# PIC32.net
KiCad netlist of a schematic drawn in Altium Designer
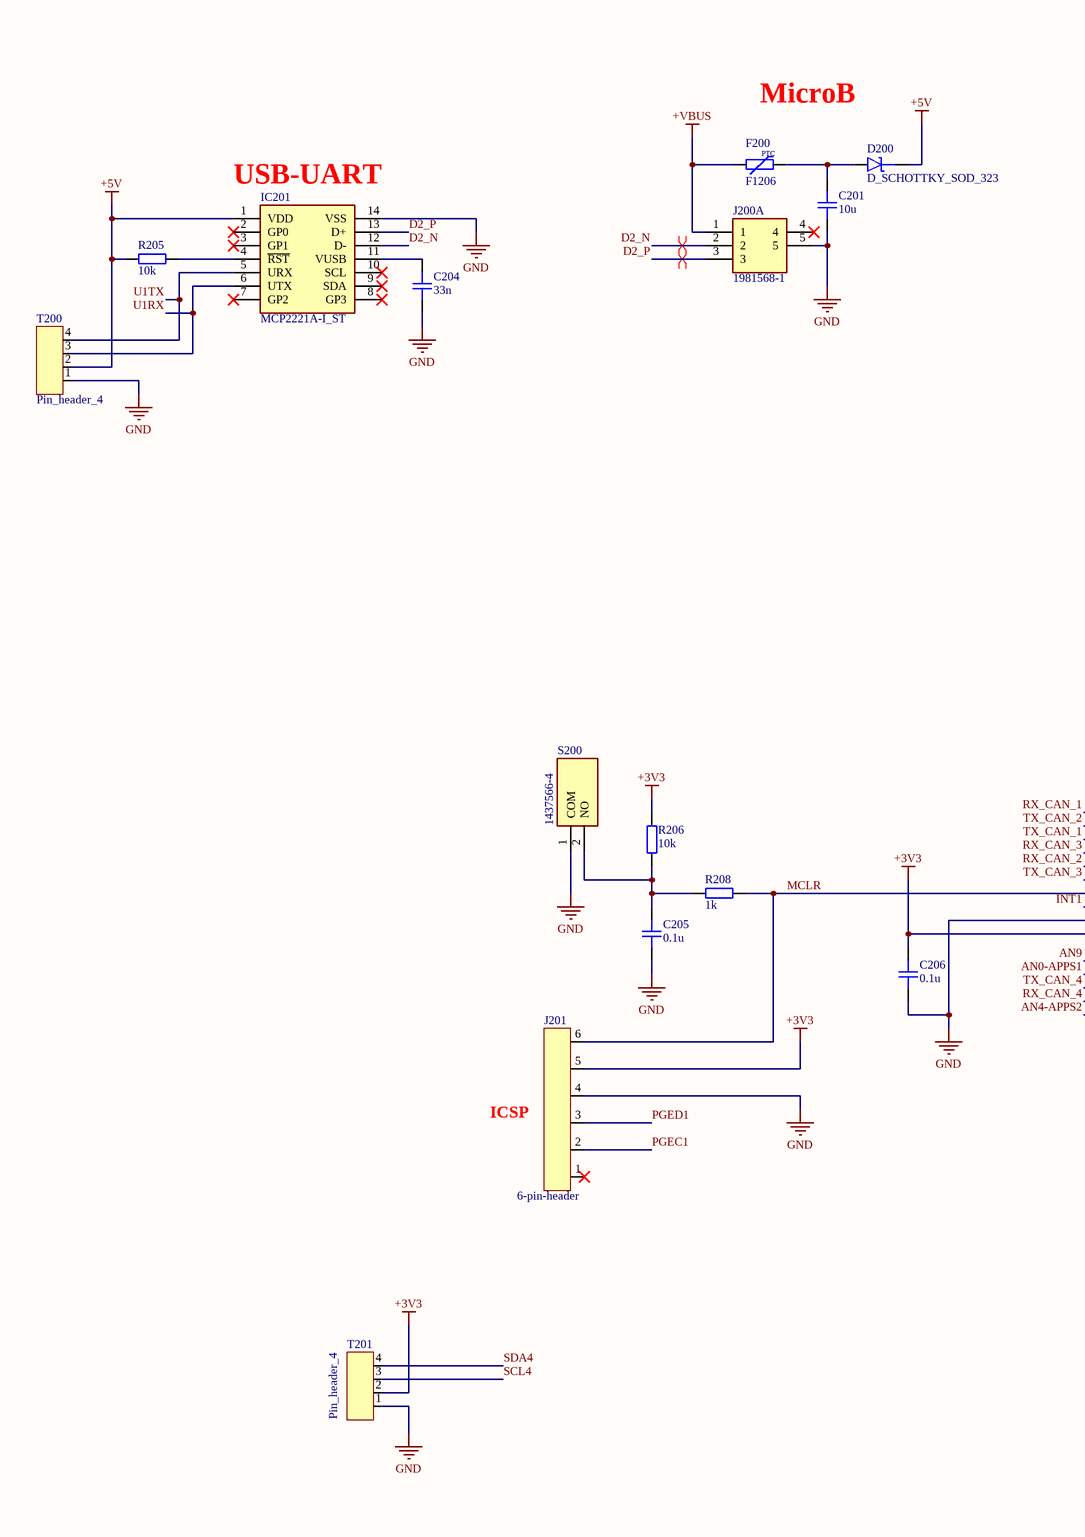
[diagram p0: PIC32.SchDoc, left]
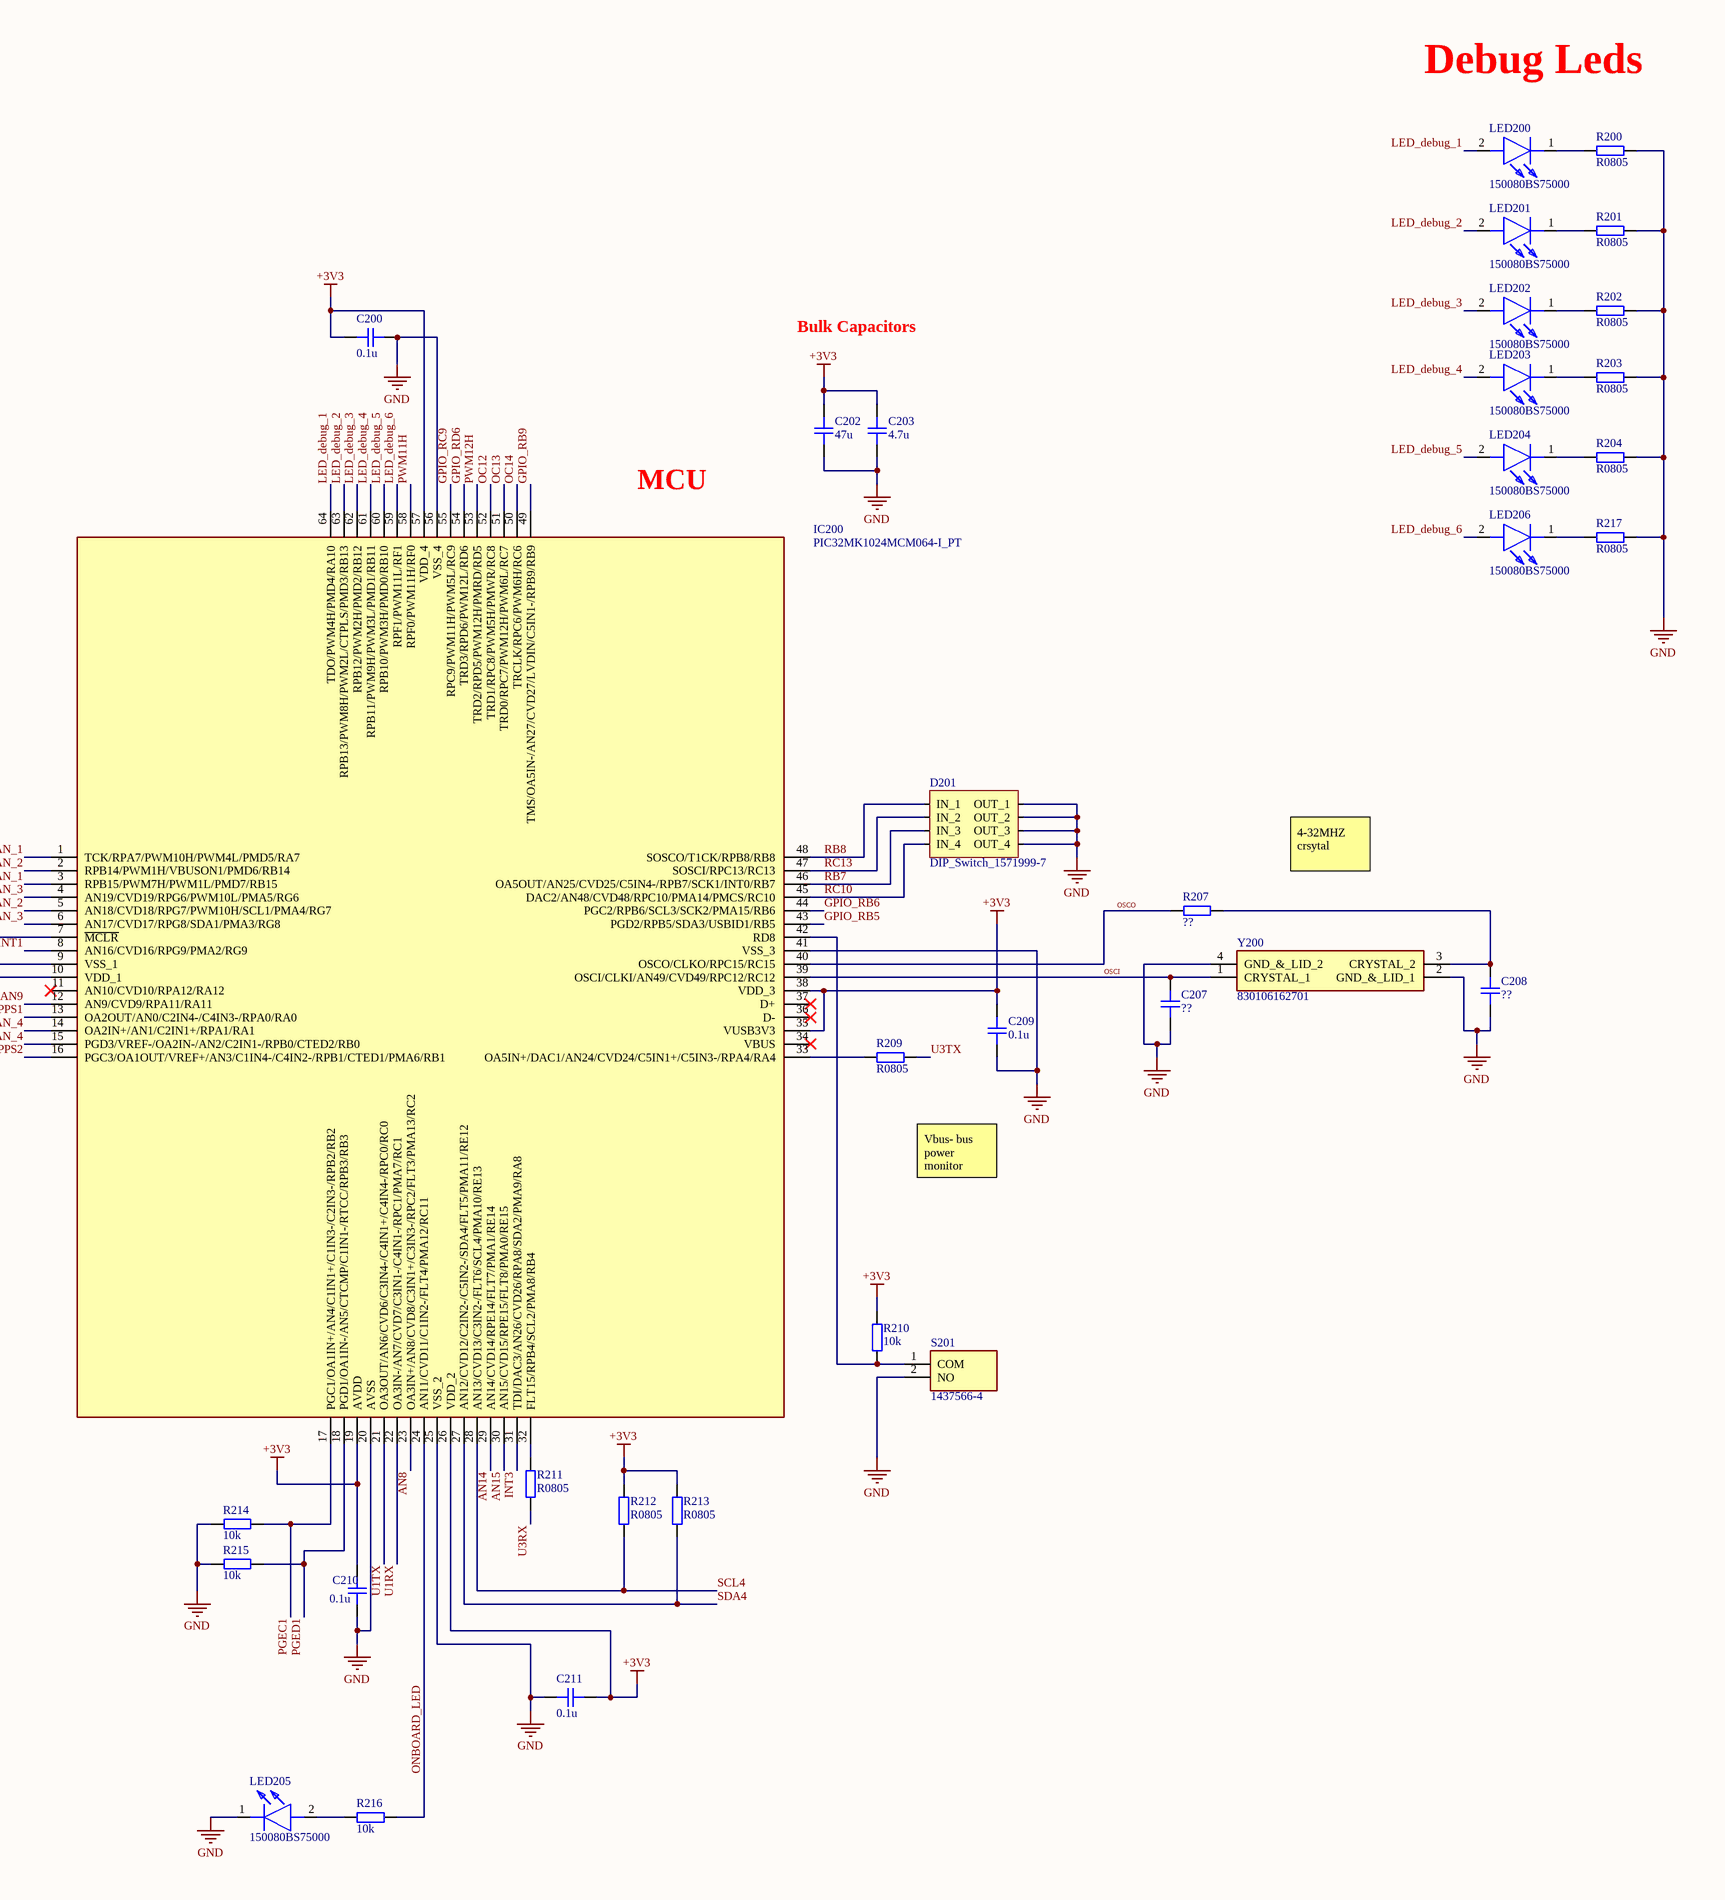
[diagram p1: PIC32.SchDoc, right]

(export (version "E")
  (design (tool "Eeschema 10.0.6"))
  (components
    (comp (ref "C200")
      (value "0.1u")
      (footprint "CAP_0805")
      (description "Capacitor SMD 0805 16V")
      (libsource (lib "Pedro_Integrated_Library") (part "CAP_0805_16V"))
    )
    (comp (ref "C201")
      (value "10u")
      (footprint "CAP_0805")
      (description "Capacitor SMD 0805 10V")
      (libsource (lib "Schematic-Lib-PhilsLab") (part "CAP_0805_10V"))
    )
    (comp (ref "C202")
      (value "47u")
      (footprint "CAP_0805")
      (description "Capacitor SMD 0805 16V")
      (libsource (lib "Pedro_Integrated_Library") (part "CAP_0805_16V"))
    )
    (comp (ref "C203")
      (value "4.7u")
      (footprint "CAP_0805")
      (description "Capacitor SMD 0805 16V")
      (libsource (lib "Pedro_Integrated_Library") (part "CAP_0805_16V"))
    )
    (comp (ref "C204")
      (value "33n")
      (footprint "CAP_0805")
      (description "Capacitor SMD 0805 10V")
      (libsource (lib "Schematic-Lib-PhilsLab") (part "CAP_0805_10V"))
    )
    (comp (ref "C205")
      (value "0.1u")
      (footprint "CAP_0805")
      (description "Capacitor SMD 0805 16V")
      (libsource (lib "Pedro_Integrated_Library") (part "CAP_0805_16V"))
    )
    (comp (ref "C206")
      (value "0.1u")
      (footprint "CAP_0805")
      (description "Capacitor SMD 0805 16V")
      (libsource (lib "Pedro_Integrated_Library") (part "CAP_0805_16V"))
    )
    (comp (ref "C207")
      (value "??")
      (footprint "CAP_0805")
      (description "Capacitor SMD 0805 16V")
      (libsource (lib "Pedro_Integrated_Library") (part "CAP_0805_16V"))
    )
    (comp (ref "C208")
      (value "??")
      (footprint "CAP_0805")
      (description "Capacitor SMD 0805 16V")
      (libsource (lib "Pedro_Integrated_Library") (part "CAP_0805_16V"))
    )
    (comp (ref "C209")
      (value "0.1u")
      (footprint "CAP_0805")
      (description "Capacitor SMD 0805 16V")
      (libsource (lib "Pedro_Integrated_Library") (part "CAP_0805_16V"))
    )
    (comp (ref "C210")
      (value "0.1u")
      (footprint "CAP_0805")
      (description "Capacitor SMD 0805 16V")
      (libsource (lib "Pedro_Integrated_Library") (part "CAP_0805_16V"))
    )
    (comp (ref "C211")
      (value "0.1u")
      (footprint "CAP_0805")
      (description "Capacitor SMD 0805 16V")
      (libsource (lib "Pedro_Integrated_Library") (part "CAP_0805_16V"))
    )
    (comp (ref "D200")
      (value "D_SCHOTTKY_SOD_323")
      (footprint "SOD-323")
      (description "Diode Schottky SMD SOD-323")
      (libsource (lib "PhilsLab") (part "D_SCHOTTKY_SOD_323"))
    )
    (comp (ref "D201")
      (value "DIP_Switch_1571999-7")
      (footprint "DIP_Switch_1571999-7 - duplicate")
      (libsource (lib "Pedro_sch_lib") (part "DIP_Switch_1571999-7"))
    )
    (comp (ref "F200")
      (value "F1206")
      (footprint "FUSE_1206")
      (description "Fuse PPTC SMD 1206")
      (libsource (lib "Schematic-Lib-PhilsLab") (part "FUSE_PPTC_1206"))
    )
    (comp (ref "IC200")
      (value "PIC32MK1024MCM064-I_PT")
      (footprint "QFP50P1200X1200X120-64N")
      (description "Integrated Circuit")
      (fields
        (field (name "MANUFACTURER_PART_NUMBER") "PIC32MK1024MCM064-I/PT")
        (field (name "MOUSER PART NUMBER") "579-2MK1024MCM064IPT")
      )
      (libsource (lib "Pedro_Integrated_Library") (part "PIC32MK1024MCM064-I_PT"))
    )
    (comp (ref "IC201")
      (value "MCP2221A-I_ST")
      (footprint "SOP65P640X120-14N")
      (description "Integrated Circuit")
      (fields
        (field (name "MANUFACTURER_PART_NUMBER") "MCP2221A-I/ST")
        (field (name "MOUSER PART NUMBER") "579-MCP2221A-I/ST")
      )
      (libsource (lib "*") (part "MCP2221A-I_ST"))
    )
    (comp (ref "J200")
      (value "1981568-1")
      (footprint "1981568-1")
      (description "Connector")
      (fields (field (name "MOUSER PART NUMBER") "571-1981568-1"))
      (libsource (lib "Pedro_sch_lib") (part "1981568-1"))
    )
    (comp (ref "J201")
      (value "6-pin-header")
      (footprint "G800W302018EU")
      (description "Pin Header 6 Position 2.54mm Pitch")
      (fields
        (field (name "MANUFACTURER") "Amphenol")
        (field (name "MANUFACTURER PART NUMBER") "G800W302018EU")
      )
      (libsource (lib "PhilsLab") (part "G800W302018EU"))
    )
    (comp (ref "LED200")
      (value "150080BS75000")
      (footprint "LEDC2012X80N")
      (description "LED")
      (fields (field (name "MOUSER PART NUMBER") "710-150080BS75000"))
      (libsource (lib "Pedro_Integrated_Library") (part "150080BS75000"))
    )
    (comp (ref "LED201")
      (value "150080BS75000")
      (footprint "LEDC2012X80N")
      (description "LED")
      (fields (field (name "MOUSER PART NUMBER") "710-150080BS75000"))
      (libsource (lib "Pedro_Integrated_Library") (part "150080BS75000"))
    )
    (comp (ref "LED202")
      (value "150080BS75000")
      (footprint "LEDC2012X80N")
      (description "LED")
      (fields (field (name "MOUSER PART NUMBER") "710-150080BS75000"))
      (libsource (lib "Pedro_Integrated_Library") (part "150080BS75000"))
    )
    (comp (ref "LED203")
      (value "150080BS75000")
      (footprint "LEDC2012X80N")
      (description "LED")
      (fields (field (name "MOUSER PART NUMBER") "710-150080BS75000"))
      (libsource (lib "Pedro_Integrated_Library") (part "150080BS75000"))
    )
    (comp (ref "LED204")
      (value "150080BS75000")
      (footprint "LEDC2012X80N")
      (description "LED")
      (fields (field (name "MOUSER PART NUMBER") "710-150080BS75000"))
      (libsource (lib "Pedro_Integrated_Library") (part "150080BS75000"))
    )
    (comp (ref "LED205")
      (value "150080BS75000")
      (footprint "LEDC2012X80N")
      (description "LED")
      (fields (field (name "MOUSER PART NUMBER") "710-150080BS75000"))
      (libsource (lib "Pedro_Integrated_Library") (part "150080BS75000"))
    )
    (comp (ref "LED206")
      (value "150080BS75000")
      (footprint "LEDC2012X80N")
      (description "LED")
      (fields (field (name "MOUSER PART NUMBER") "710-150080BS75000"))
      (libsource (lib "Pedro_Integrated_Library") (part "150080BS75000"))
    )
    (comp (ref "R200")
      (value "R0805")
      (footprint "RES_0805")
      (description "Resistor SMD 0805")
      (libsource (lib "Schematic-Lib-PhilsLab") (part "RES_0805"))
    )
    (comp (ref "R201")
      (value "R0805")
      (footprint "RES_0805")
      (description "Resistor SMD 0805")
      (libsource (lib "Schematic-Lib-PhilsLab") (part "RES_0805"))
    )
    (comp (ref "R202")
      (value "R0805")
      (footprint "RES_0805")
      (description "Resistor SMD 0805")
      (libsource (lib "Schematic-Lib-PhilsLab") (part "RES_0805"))
    )
    (comp (ref "R203")
      (value "R0805")
      (footprint "RES_0805")
      (description "Resistor SMD 0805")
      (libsource (lib "Schematic-Lib-PhilsLab") (part "RES_0805"))
    )
    (comp (ref "R204")
      (value "R0805")
      (footprint "RES_0805")
      (description "Resistor SMD 0805")
      (libsource (lib "Schematic-Lib-PhilsLab") (part "RES_0805"))
    )
    (comp (ref "R205")
      (value "10k")
      (footprint "RES_0805")
      (description "Resistor SMD 0805")
      (libsource (lib "Pedro_Integrated_Library") (part "RES_0805"))
    )
    (comp (ref "R206")
      (value "10k")
      (footprint "RES_0805")
      (description "Resistor SMD 0805")
      (libsource (lib "Pedro_Integrated_Library") (part "RES_0805"))
    )
    (comp (ref "R207")
      (value "??")
      (footprint "RES_0805")
      (description "Resistor SMD 0805")
      (libsource (lib "Pedro_Integrated_Library") (part "RES_0805"))
    )
    (comp (ref "R208")
      (value "1k")
      (footprint "RES_0805")
      (description "Resistor SMD 0805")
      (libsource (lib "Pedro_Integrated_Library") (part "RES_0805"))
    )
    (comp (ref "R209")
      (value "R0805")
      (footprint "RES_0805")
      (description "Resistor SMD 0805")
      (libsource (lib "Schematic-Lib-PhilsLab") (part "RES_0805"))
    )
    (comp (ref "R210")
      (value "10k")
      (footprint "RES_0805")
      (description "Resistor SMD 0805")
      (libsource (lib "Pedro_Integrated_Library") (part "RES_0805"))
    )
    (comp (ref "R211")
      (value "R0805")
      (footprint "RES_0805")
      (description "Resistor SMD 0805")
      (libsource (lib "Schematic-Lib-PhilsLab") (part "RES_0805"))
    )
    (comp (ref "R212")
      (value "R0805")
      (footprint "RES_0805")
      (description "Resistor SMD 0805")
      (libsource (lib "Schematic-Lib-PhilsLab") (part "RES_0805"))
    )
    (comp (ref "R213")
      (value "R0805")
      (footprint "RES_0805")
      (description "Resistor SMD 0805")
      (libsource (lib "Schematic-Lib-PhilsLab") (part "RES_0805"))
    )
    (comp (ref "R214")
      (value "10k")
      (footprint "RES_0805")
      (description "Resistor SMD 0805")
      (libsource (lib "Pedro_Integrated_Library") (part "RES_0805"))
    )
    (comp (ref "R215")
      (value "10k")
      (footprint "RES_0805")
      (description "Resistor SMD 0805")
      (libsource (lib "Pedro_Integrated_Library") (part "RES_0805"))
    )
    (comp (ref "R216")
      (value "10k")
      (footprint "RES_0805")
      (description "Resistor SMD 0805")
      (libsource (lib "Pedro_Integrated_Library") (part "RES_0805"))
    )
    (comp (ref "R217")
      (value "R0805")
      (footprint "RES_0805")
      (description "Resistor SMD 0805")
      (libsource (lib "Schematic-Lib-PhilsLab") (part "RES_0805"))
    )
    (comp (ref "S200")
      (value "1437566-4")
      (footprint "14375664")
      (description "Switch")
      (libsource (lib "Pedro_sch_lib") (part "1437566-4"))
    )
    (comp (ref "S201")
      (value "1437566-4")
      (footprint "14375664")
      (description "Switch")
      (libsource (lib "") (part "1437566-4_1"))
    )
    (comp (ref "T200")
      (value "Pin_header_4")
      (footprint "Pin_header_4")
      (libsource (lib "Pedro_Integrated_Library") (part "Pin_header_4"))
    )
    (comp (ref "T201")
      (value "Pin_header_4")
      (footprint "Pin_header_4")
      (libsource (lib "Pedro_Integrated_Library") (part "Pin_header_4"))
    )
    (comp (ref "Y200")
      (value "830106162701")
      (footprint "Pedro_pcb_lib:830106162701")
      (description "Crystal or Oscillator")
      (fields (field (name "MOUSER PART NUMBER") "710-830106162701"))
      (libsource (lib "*") (part "830106162701"))
    )
  )
  (nets
    (net (code "1") (name "+3V3") (class "Default")
      (node (ref "C200") (pin "1") (pinfunction "1_1") (pintype "passive"))
      (node (ref "C202") (pin "1") (pinfunction "1_1") (pintype "passive"))
      (node (ref "C203") (pin "1") (pinfunction "1_1") (pintype "passive"))
      (node (ref "C206") (pin "2") (pinfunction "2_2") (pintype "passive"))
      (node (ref "C209") (pin "1") (pinfunction "1_1") (pintype "passive"))
      (node (ref "C210") (pin "2") (pinfunction "2_2") (pintype "passive"))
      (node (ref "C211") (pin "1") (pinfunction "1_1") (pintype "passive"))
      (node (ref "IC200") (pin "10") (pinfunction "VDD_1_10") (pintype "passive"))
      (node (ref "IC200") (pin "19") (pinfunction "AVDD_19") (pintype "passive"))
      (node (ref "IC200") (pin "26") (pinfunction "VDD_2_26") (pintype "passive"))
      (node (ref "IC200") (pin "35") (pinfunction "VUSB3V3_35") (pintype "passive"))
      (node (ref "IC200") (pin "38") (pinfunction "VDD_3_38") (pintype "passive"))
      (node (ref "IC200") (pin "57") (pinfunction "VDD_4_57") (pintype "passive"))
      (node (ref "J201") (pin "5") (pinfunction "5_5") (pintype "passive"))
      (node (ref "R206") (pin "1") (pinfunction "1_1") (pintype "passive"))
      (node (ref "R210") (pin "2") (pinfunction "2_2") (pintype "passive"))
      (node (ref "R212") (pin "1") (pinfunction "1_1") (pintype "passive"))
      (node (ref "R213") (pin "1") (pinfunction "1_1") (pintype "passive"))
      (node (ref "T201") (pin "2") (pintype "bidirectional"))
    )
    (net (code "2") (name "+5V") (class "Default")
      (node (ref "D200") (pin "K") (pinfunction "K_K") (pintype "passive"))
      (node (ref "IC201") (pin "1") (pinfunction "VDD_1") (pintype "passive"))
      (node (ref "R205") (pin "1") (pinfunction "1_1") (pintype "passive"))
      (node (ref "T200") (pin "2") (pintype "bidirectional"))
    )
    (net (code "3") (name "+VBUS") (class "Default")
      (node (ref "F200") (pin "1") (pinfunction "1_1") (pintype "passive"))
      (node (ref "J200") (pin "1") (pinfunction "1_1") (pintype "passive"))
    )
    (net (code "4") (name "/AN0-APPS1") (class "Default")
      (node (ref "IC200") (pin "13") (pinfunction "OA2OUT/AN0/C2IN4-/C4IN3-/RPA0/RA0_13") (pintype "passive"))
    )
    (net (code "5") (name "/AN4-APPS2") (class "Default")
      (node (ref "IC200") (pin "16") (pinfunction "PGC3/OA1OUT/VREF+/AN3/C1IN4-/C4IN2-/RPB1/CTED1/PMA6/RB1_16") (pintype "passive"))
    )
    (net (code "6") (name "/AN8") (class "Default")
      (node (ref "IC200") (pin "23") (pinfunction "OA3IN+/AN8/CVD8/C3IN1+/C3IN3-/RPC2/FLT3/PMA13/RC2_23") (pintype "passive"))
    )
    (net (code "7") (name "/AN9") (class "Default")
      (node (ref "IC200") (pin "12") (pinfunction "AN9/CVD9/RPA11/RA11_12") (pintype "passive"))
    )
    (net (code "8") (name "/AN14") (class "Default")
      (node (ref "IC200") (pin "29") (pinfunction "AN14/CVD14/RPE14/FLT7/PMA1/RE14_29") (pintype "passive"))
    )
    (net (code "9") (name "/AN15") (class "Default")
      (node (ref "IC200") (pin "30") (pinfunction "AN15/CVD15/RPE15/FLT8/PMA0/RE15_30") (pintype "passive"))
    )
    (net (code "10") (name "/D2_N") (class "Default")
      (node (ref "IC201") (pin "12") (pinfunction "D-_12") (pintype "passive"))
      (node (ref "J200") (pin "2") (pinfunction "2_2") (pintype "passive"))
    )
    (net (code "11") (name "/D2_P") (class "Default")
      (node (ref "IC201") (pin "13") (pinfunction "D+_13") (pintype "passive"))
      (node (ref "J200") (pin "3") (pinfunction "3_3") (pintype "passive"))
    )
    (net (code "12") (name "/GPIO_RB5") (class "Default")
      (node (ref "IC200") (pin "43") (pinfunction "PGD2/RPB5/SDA3/USBID1/RB5_43") (pintype "passive"))
    )
    (net (code "13") (name "/GPIO_RB6") (class "Default")
      (node (ref "IC200") (pin "44") (pinfunction "PGC2/RPB6/SCL3/SCK2/PMA15/RB6_44") (pintype "passive"))
    )
    (net (code "14") (name "/GPIO_RB9") (class "Default")
      (node (ref "IC200") (pin "49") (pinfunction "TMS/OA5IN-/AN27/CVD27/LVDIN/C5IN1-/RPB9/RB9_49") (pintype "passive"))
    )
    (net (code "15") (name "/GPIO_RC9") (class "Default")
      (node (ref "IC200") (pin "55") (pinfunction "RPC9/PWM11H/PWM5L/RC9_55") (pintype "passive"))
    )
    (net (code "16") (name "/GPIO_RD6") (class "Default")
      (node (ref "IC200") (pin "54") (pinfunction "TRD3/RPD6/PWM12L/RD6_54") (pintype "passive"))
    )
    (net (code "17") (name "/INT1") (class "Default")
      (node (ref "IC200") (pin "8") (pinfunction "AN16/CVD16/RPG9/PMA2/RG9_8") (pintype "passive"))
    )
    (net (code "18") (name "/INT3") (class "Default")
      (node (ref "IC200") (pin "31") (pinfunction "TDI/DAC3/AN26/CVD26/RPA8/SDA2/PMA9/RA8_31") (pintype "passive"))
    )
    (net (code "19") (name "/LED_debug_1") (class "Default")
      (node (ref "IC200") (pin "64") (pinfunction "TDO/PWM4H/PMD4/RA10_64") (pintype "passive"))
      (node (ref "LED200") (pin "2") (pinfunction "A_2") (pintype "passive"))
    )
    (net (code "20") (name "/LED_debug_2") (class "Default")
      (node (ref "IC200") (pin "63") (pinfunction "RPB13/PWM8H/PWM2L/CTPLS/PMD3/RB13_63") (pintype "passive"))
      (node (ref "LED201") (pin "2") (pinfunction "A_2") (pintype "passive"))
    )
    (net (code "21") (name "/LED_debug_3") (class "Default")
      (node (ref "IC200") (pin "62") (pinfunction "RPB12/PWM2H/PMD2/RB12_62") (pintype "passive"))
      (node (ref "LED202") (pin "2") (pinfunction "A_2") (pintype "passive"))
    )
    (net (code "22") (name "/LED_debug_4") (class "Default")
      (node (ref "IC200") (pin "61") (pinfunction "RPB11/PWM9H/PWM3L/PMD1/RB11_61") (pintype "passive"))
      (node (ref "LED203") (pin "2") (pinfunction "A_2") (pintype "passive"))
    )
    (net (code "23") (name "/LED_debug_5") (class "Default")
      (node (ref "IC200") (pin "60") (pinfunction "RPB10/PWM3H/PMD0/RB10_60") (pintype "passive"))
      (node (ref "LED204") (pin "2") (pinfunction "A_2") (pintype "passive"))
    )
    (net (code "24") (name "/LED_debug_6") (class "Default")
      (node (ref "IC200") (pin "59") (pinfunction "RPF1/PWM11L/RF1_59") (pintype "passive"))
      (node (ref "LED206") (pin "2") (pinfunction "A_2") (pintype "passive"))
    )
    (net (code "25") (name "/MCLR") (class "Default")
      (node (ref "IC200") (pin "7") (pinfunction "~{MCLR}_7") (pintype "passive"))
      (node (ref "J201") (pin "6") (pinfunction "6_6") (pintype "passive"))
      (node (ref "R208") (pin "1") (pinfunction "1_1") (pintype "passive"))
    )
    (net (code "26") (name "/OC12") (class "Default")
      (node (ref "IC200") (pin "52") (pinfunction "TRD1/RPC8/PWM5H/PMWR/RC8_52") (pintype "passive"))
    )
    (net (code "27") (name "/OC13") (class "Default")
      (node (ref "IC200") (pin "51") (pinfunction "TRD0/RPC7/PWM12H/PWM6L/RC7_51") (pintype "passive"))
    )
    (net (code "28") (name "/OC14") (class "Default")
      (node (ref "IC200") (pin "50") (pinfunction "TRCLK/RPC6/PWM6H/RC6_50") (pintype "passive"))
    )
    (net (code "29") (name "/ONBOARD_LED") (class "Default")
      (node (ref "IC200") (pin "24") (pinfunction "AN11/CVD11/C1IN2-/FLT4/PMA12/RC11_24") (pintype "passive"))
      (node (ref "R216") (pin "1") (pinfunction "1_1") (pintype "passive"))
    )
    (net (code "30") (name "/OSCI") (class "Default")
      (node (ref "C207") (pin "2") (pinfunction "2_2") (pintype "passive"))
      (node (ref "IC200") (pin "39") (pinfunction "OSCI/CLKI/AN49/CVD49/RPC12/RC12_39") (pintype "passive"))
      (node (ref "Y200") (pin "1") (pinfunction "CRYSTAL_1_1") (pintype "passive"))
    )
    (net (code "31") (name "/OSCO") (class "Default")
      (node (ref "IC200") (pin "40") (pinfunction "OSCO/CLKO/RPC15/RC15_40") (pintype "passive"))
      (node (ref "R207") (pin "2") (pinfunction "2_2") (pintype "passive"))
    )
    (net (code "32") (name "/PGEC1") (class "Default")
      (node (ref "IC200") (pin "17") (pinfunction "PGC1/OA1IN+/AN4/C1IN1+/C1IN3-/C2IN3-/RPB2/RB2_17") (pintype "passive"))
      (node (ref "J201") (pin "2") (pinfunction "2_2") (pintype "passive"))
      (node (ref "R214") (pin "1") (pinfunction "1_1") (pintype "passive"))
    )
    (net (code "33") (name "/PGED1") (class "Default")
      (node (ref "IC200") (pin "18") (pinfunction "PGD1/OA1IN-/AN5/CTCMP/C1IN1-/RTCC/RPB3/RB3_18") (pintype "passive"))
      (node (ref "J201") (pin "3") (pinfunction "3_3") (pintype "passive"))
      (node (ref "R215") (pin "1") (pinfunction "1_1") (pintype "passive"))
    )
    (net (code "34") (name "/PWM11H") (class "Default")
      (node (ref "IC200") (pin "58") (pinfunction "RPF0/PWM11H/RF0_58") (pintype "passive"))
    )
    (net (code "35") (name "/PWM12H") (class "Default")
      (node (ref "IC200") (pin "53") (pinfunction "TRD2/RPD5/PWM12H/PMRD/RD5_53") (pintype "passive"))
    )
    (net (code "36") (name "/RB7") (class "Default")
      (node (ref "D201") (pin "3") (pinfunction "IN_3_3") (pintype "passive"))
      (node (ref "IC200") (pin "46") (pinfunction "OA5OUT/AN25/CVD25/C5IN4-/RPB7/SCK1/INT0/RB7_46") (pintype "passive"))
    )
    (net (code "37") (name "/RB8") (class "Default")
      (node (ref "D201") (pin "1") (pinfunction "IN_1_1") (pintype "passive"))
      (node (ref "IC200") (pin "48") (pinfunction "SOSCO/T1CK/RPB8/RB8_48") (pintype "passive"))
    )
    (net (code "38") (name "/RC10") (class "Default")
      (node (ref "D201") (pin "4") (pinfunction "IN_4_4") (pintype "passive"))
      (node (ref "IC200") (pin "45") (pinfunction "DAC2/AN48/CVD48/RPC10/PMA14/PMCS/RC10_45") (pintype "passive"))
    )
    (net (code "39") (name "/RC13") (class "Default")
      (node (ref "D201") (pin "2") (pinfunction "IN_2_2") (pintype "passive"))
      (node (ref "IC200") (pin "47") (pinfunction "SOSCI/RPC13/RC13_47") (pintype "passive"))
    )
    (net (code "40") (name "/RX_CAN_1") (class "Default")
      (node (ref "IC200") (pin "1") (pinfunction "TCK/RPA7/PWM10H/PWM4L/PMD5/RA7_1") (pintype "passive"))
    )
    (net (code "41") (name "/RX_CAN_2") (class "Default")
      (node (ref "IC200") (pin "5") (pinfunction "AN18/CVD18/RPG7/PWM10H/SCL1/PMA4/RG7_5") (pintype "passive"))
    )
    (net (code "42") (name "/RX_CAN_3") (class "Default")
      (node (ref "IC200") (pin "4") (pinfunction "AN19/CVD19/RPG6/PWM10L/PMA5/RG6_4") (pintype "passive"))
    )
    (net (code "43") (name "/RX_CAN_4") (class "Default")
      (node (ref "IC200") (pin "15") (pinfunction "PGD3/VREF-/OA2IN-/AN2/C2IN1-/RPB0/CTED2/RB0_15") (pintype "passive"))
    )
    (net (code "44") (name "/SCL4") (class "Default")
      (node (ref "IC200") (pin "28") (pinfunction "AN13/CVD13/C3IN2-/FLT6/SCL4/PMA10/RE13_28") (pintype "passive"))
      (node (ref "R212") (pin "2") (pinfunction "2_2") (pintype "passive"))
      (node (ref "T201") (pin "3") (pintype "bidirectional"))
    )
    (net (code "45") (name "/SDA4") (class "Default")
      (node (ref "IC200") (pin "27") (pinfunction "AN12/CVD12/C2IN2-/C5IN2-/SDA4/FLT5/PMA11/RE12_27") (pintype "passive"))
      (node (ref "R213") (pin "2") (pinfunction "2_2") (pintype "passive"))
      (node (ref "T201") (pin "4") (pintype "bidirectional"))
    )
    (net (code "46") (name "/TX_CAN_1") (class "Default")
      (node (ref "IC200") (pin "3") (pinfunction "RPB15/PWM7H/PWM1L/PMD7/RB15_3") (pintype "passive"))
    )
    (net (code "47") (name "/TX_CAN_2") (class "Default")
      (node (ref "IC200") (pin "2") (pinfunction "RPB14/PWM1H/VBUSON1/PMD6/RB14_2") (pintype "passive"))
    )
    (net (code "48") (name "/TX_CAN_3") (class "Default")
      (node (ref "IC200") (pin "6") (pinfunction "AN17/CVD17/RPG8/SDA1/PMA3/RG8_6") (pintype "passive"))
    )
    (net (code "49") (name "/TX_CAN_4") (class "Default")
      (node (ref "IC200") (pin "14") (pinfunction "OA2IN+/AN1/C2IN1+/RPA1/RA1_14") (pintype "passive"))
    )
    (net (code "50") (name "/U1RX") (class "Default")
      (node (ref "IC200") (pin "22") (pinfunction "OA3IN-/AN7/CVD7/C3IN1-/C4IN1-/RPC1/PMA7/RC1_22") (pintype "passive"))
      (node (ref "IC201") (pin "6") (pinfunction "UTX_6") (pintype "passive"))
      (node (ref "T200") (pin "3") (pintype "bidirectional"))
    )
    (net (code "51") (name "/U1TX") (class "Default")
      (node (ref "IC200") (pin "21") (pinfunction "OA3OUT/AN6/CVD6/C3IN4-/C4IN1+/C4IN4-/RPC0/RC0_21") (pintype "passive"))
      (node (ref "IC201") (pin "5") (pinfunction "URX_5") (pintype "passive"))
      (node (ref "T200") (pin "4") (pintype "bidirectional"))
    )
    (net (code "52") (name "/U3RX") (class "Default")
      (node (ref "R211") (pin "2") (pinfunction "2_2") (pintype "passive"))
    )
    (net (code "53") (name "/U3TX") (class "Default")
      (node (ref "R209") (pin "2") (pinfunction "2_2") (pintype "passive"))
    )
    (net (code "54") (name "GND") (class "Default")
      (node (ref "C200") (pin "2") (pinfunction "2_2") (pintype "passive"))
      (node (ref "C201") (pin "2") (pinfunction "2_2") (pintype "passive"))
      (node (ref "C202") (pin "2") (pinfunction "2_2") (pintype "passive"))
      (node (ref "C203") (pin "2") (pinfunction "2_2") (pintype "passive"))
      (node (ref "C204") (pin "1") (pinfunction "1_1") (pintype "passive"))
      (node (ref "C205") (pin "1") (pinfunction "1_1") (pintype "passive"))
      (node (ref "C206") (pin "1") (pinfunction "1_1") (pintype "passive"))
      (node (ref "C207") (pin "1") (pinfunction "1_1") (pintype "passive"))
      (node (ref "C208") (pin "1") (pinfunction "1_1") (pintype "passive"))
      (node (ref "C209") (pin "2") (pinfunction "2_2") (pintype "passive"))
      (node (ref "C210") (pin "1") (pinfunction "1_1") (pintype "passive"))
      (node (ref "C211") (pin "2") (pinfunction "2_2") (pintype "passive"))
      (node (ref "D201") (pin "5") (pinfunction "OUT_4_5") (pintype "passive"))
      (node (ref "D201") (pin "6") (pinfunction "OUT_3_6") (pintype "passive"))
      (node (ref "D201") (pin "7") (pinfunction "OUT_2_7") (pintype "passive"))
      (node (ref "D201") (pin "8") (pinfunction "OUT_1_8") (pintype "passive"))
      (node (ref "IC200") (pin "20") (pinfunction "AVSS_20") (pintype "passive"))
      (node (ref "IC200") (pin "25") (pinfunction "VSS_2_25") (pintype "passive"))
      (node (ref "IC200") (pin "41") (pinfunction "VSS_3_41") (pintype "passive"))
      (node (ref "IC200") (pin "56") (pinfunction "VSS_4_56") (pintype "passive"))
      (node (ref "IC200") (pin "9") (pinfunction "VSS_1_9") (pintype "passive"))
      (node (ref "IC201") (pin "14") (pinfunction "VSS_14") (pintype "passive"))
      (node (ref "J200") (pin "5") (pinfunction "5_5") (pintype "passive"))
      (node (ref "J201") (pin "4") (pinfunction "4_4") (pintype "passive"))
      (node (ref "LED205") (pin "1") (pinfunction "K_1") (pintype "passive"))
      (node (ref "R200") (pin "1") (pinfunction "1_1") (pintype "passive"))
      (node (ref "R201") (pin "1") (pinfunction "1_1") (pintype "passive"))
      (node (ref "R202") (pin "1") (pinfunction "1_1") (pintype "passive"))
      (node (ref "R203") (pin "1") (pinfunction "1_1") (pintype "passive"))
      (node (ref "R204") (pin "1") (pinfunction "1_1") (pintype "passive"))
      (node (ref "R214") (pin "2") (pinfunction "2_2") (pintype "passive"))
      (node (ref "R215") (pin "2") (pinfunction "2_2") (pintype "passive"))
      (node (ref "R217") (pin "1") (pinfunction "1_1") (pintype "passive"))
      (node (ref "S200") (pin "1") (pinfunction "COM_1") (pintype "passive"))
      (node (ref "S201") (pin "2") (pinfunction "NO_2") (pintype "passive"))
      (node (ref "T200") (pin "1") (pintype "bidirectional"))
      (node (ref "T201") (pin "1") (pintype "bidirectional"))
      (node (ref "Y200") (pin "2") (pinfunction "GND_&_LID_1_2") (pintype "passive"))
      (node (ref "Y200") (pin "4") (pinfunction "GND_&_LID_2_4") (pintype "passive"))
    )
    (net (code "55") (name "Net-(C201-Pad1)") (class "Default")
      (node (ref "C201") (pin "1") (pinfunction "1_1") (pintype "passive"))
      (node (ref "D200") (pin "A") (pinfunction "A_A") (pintype "passive"))
      (node (ref "F200") (pin "2") (pinfunction "2_2") (pintype "passive"))
    )
    (net (code "56") (name "Net-(IC200-FLT15{slash}RPB4{slash}SCL2{slash}PMA8{slash}RB4)") (class "Default")
      (node (ref "IC200") (pin "32") (pinfunction "FLT15/RPB4/SCL2/PMA8/RB4_32") (pintype "passive"))
      (node (ref "R211") (pin "1") (pinfunction "1_1") (pintype "passive"))
    )
    (net (code "57") (name "Net-(IC200-OA5IN+{slash}DAC1{slash}AN24{slash}CVD24{slash}C5IN1+{slash}C5IN3-{slash}RPA4{slash}RA4)") (class "Default")
      (node (ref "IC200") (pin "33") (pinfunction "OA5IN+/DAC1/AN24/CVD24/C5IN1+/C5IN3-/RPA4/RA4_33") (pintype "passive"))
      (node (ref "R209") (pin "1") (pinfunction "1_1") (pintype "passive"))
    )
    (net (code "58") (name "Net-(IC200-RD8)") (class "Default")
      (node (ref "IC200") (pin "42") (pinfunction "RD8_42") (pintype "passive"))
      (node (ref "R210") (pin "1") (pinfunction "1_1") (pintype "passive"))
      (node (ref "S201") (pin "1") (pinfunction "COM_1") (pintype "passive"))
    )
    (net (code "59") (name "Net-(IC201-VUSB)") (class "Default")
      (node (ref "C204") (pin "2") (pinfunction "2_2") (pintype "passive"))
      (node (ref "IC201") (pin "11") (pinfunction "VUSB_11") (pintype "passive"))
    )
    (net (code "60") (name "Net-(IC201-~{RST})") (class "Default")
      (node (ref "IC201") (pin "4") (pinfunction "~{RST}_4") (pintype "passive"))
      (node (ref "R205") (pin "2") (pinfunction "2_2") (pintype "passive"))
    )
    (net (code "61") (name "Net-(LED200-K)") (class "Default")
      (node (ref "LED200") (pin "1") (pinfunction "K_1") (pintype "passive"))
      (node (ref "R200") (pin "2") (pinfunction "2_2") (pintype "passive"))
    )
    (net (code "62") (name "Net-(LED201-K)") (class "Default")
      (node (ref "LED201") (pin "1") (pinfunction "K_1") (pintype "passive"))
      (node (ref "R201") (pin "2") (pinfunction "2_2") (pintype "passive"))
    )
    (net (code "63") (name "Net-(LED202-K)") (class "Default")
      (node (ref "LED202") (pin "1") (pinfunction "K_1") (pintype "passive"))
      (node (ref "R202") (pin "2") (pinfunction "2_2") (pintype "passive"))
    )
    (net (code "64") (name "Net-(LED203-K)") (class "Default")
      (node (ref "LED203") (pin "1") (pinfunction "K_1") (pintype "passive"))
      (node (ref "R203") (pin "2") (pinfunction "2_2") (pintype "passive"))
    )
    (net (code "65") (name "Net-(LED204-K)") (class "Default")
      (node (ref "LED204") (pin "1") (pinfunction "K_1") (pintype "passive"))
      (node (ref "R204") (pin "2") (pinfunction "2_2") (pintype "passive"))
    )
    (net (code "66") (name "Net-(LED205-A)") (class "Default")
      (node (ref "LED205") (pin "2") (pinfunction "A_2") (pintype "passive"))
      (node (ref "R216") (pin "2") (pinfunction "2_2") (pintype "passive"))
    )
    (net (code "67") (name "Net-(LED206-K)") (class "Default")
      (node (ref "LED206") (pin "1") (pinfunction "K_1") (pintype "passive"))
      (node (ref "R217") (pin "2") (pinfunction "2_2") (pintype "passive"))
    )
    (net (code "68") (name "Net-(S200-NO)") (class "Default")
      (node (ref "C205") (pin "2") (pinfunction "2_2") (pintype "passive"))
      (node (ref "R206") (pin "2") (pinfunction "2_2") (pintype "passive"))
      (node (ref "R208") (pin "2") (pinfunction "2_2") (pintype "passive"))
      (node (ref "S200") (pin "2") (pinfunction "NO_2") (pintype "passive"))
    )
    (net (code "69") (name "Net-(Y200-CRYSTAL_2)") (class "Default")
      (node (ref "C208") (pin "2") (pinfunction "2_2") (pintype "passive"))
      (node (ref "R207") (pin "1") (pinfunction "1_1") (pintype "passive"))
      (node (ref "Y200") (pin "3") (pinfunction "CRYSTAL_2_3") (pintype "passive"))
    )
    (net (code "70") (name "unconnected-(IC200-AN10{slash}CVD10{slash}RPA12{slash}RA12-Pad11)") (class "Default")
      (node (ref "IC200") (pin "11") (pinfunction "AN10/CVD10/RPA12/RA12_11") (pintype "passive+no_connect"))
    )
    (net (code "71") (name "unconnected-(IC200-D+-Pad37)") (class "Default")
      (node (ref "IC200") (pin "37") (pinfunction "D+_37") (pintype "passive+no_connect"))
    )
    (net (code "72") (name "unconnected-(IC200-D--Pad36)") (class "Default")
      (node (ref "IC200") (pin "36") (pinfunction "D-_36") (pintype "passive+no_connect"))
    )
    (net (code "73") (name "unconnected-(IC200-VBUS-Pad34)") (class "Default")
      (node (ref "IC200") (pin "34") (pinfunction "VBUS_34") (pintype "passive+no_connect"))
    )
    (net (code "74") (name "unconnected-(IC201-GP0-Pad2)") (class "Default")
      (node (ref "IC201") (pin "2") (pinfunction "GP0_2") (pintype "passive+no_connect"))
    )
    (net (code "75") (name "unconnected-(IC201-GP1-Pad3)") (class "Default")
      (node (ref "IC201") (pin "3") (pinfunction "GP1_3") (pintype "passive+no_connect"))
    )
    (net (code "76") (name "unconnected-(IC201-GP2-Pad7)") (class "Default")
      (node (ref "IC201") (pin "7") (pinfunction "GP2_7") (pintype "passive+no_connect"))
    )
    (net (code "77") (name "unconnected-(IC201-GP3-Pad8)") (class "Default")
      (node (ref "IC201") (pin "8") (pinfunction "GP3_8") (pintype "passive+no_connect"))
    )
    (net (code "78") (name "unconnected-(IC201-SCL-Pad10)") (class "Default")
      (node (ref "IC201") (pin "10") (pinfunction "SCL_10") (pintype "passive+no_connect"))
    )
    (net (code "79") (name "unconnected-(IC201-SDA-Pad9)") (class "Default")
      (node (ref "IC201") (pin "9") (pinfunction "SDA_9") (pintype "passive+no_connect"))
    )
    (net (code "80") (name "unconnected-(J200-Pad4)") (class "Default")
      (node (ref "J200") (pin "4") (pinfunction "4_4") (pintype "passive+no_connect"))
    )
    (net (code "81") (name "unconnected-(J201-Pad1)") (class "Default")
      (node (ref "J201") (pin "1") (pinfunction "1_1") (pintype "passive+no_connect"))
    )
  )
)
